# RTC.net
KiCad netlist of a schematic drawn in Altium Designer
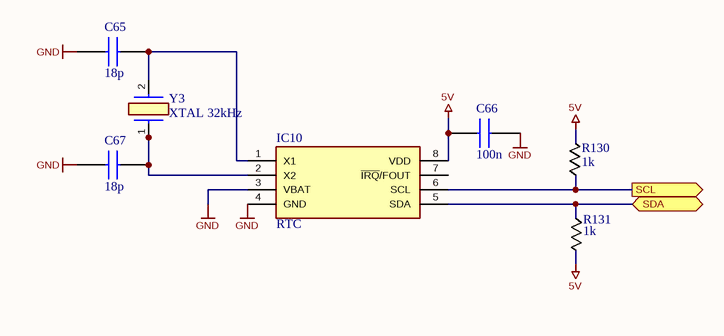
[diagram p0: RTC.SchDoc]

(export (version "E")
  (design (tool "Eeschema 10.0.6"))
  (components
    (comp (ref "C65")
      (value "18p")
      (footprint "0603 CAP")
      (description "CC0603JRNPO9BN180")
      (fields
        (field (name "MANUFACTURER_PART_NUMBER") "GRM188R72A103KA01D")
        (field (name "MOUSER PART NUMBER") "81-GRM188R72A103KA1D")
      )
      (libsource (lib "IGAS Elements") (part "0603 CAP"))
    )
    (comp (ref "C66")
      (value "100n")
      (footprint "0603 CAP")
      (description "CC0603KRX7R9BB104")
      (fields
        (field (name "MANUFACTURER_PART_NUMBER") "GRM188R72A103KA01D")
        (field (name "MOUSER PART NUMBER") "81-GRM188R72A103KA1D")
      )
      (libsource (lib "IGAS Elements") (part "0603 CAP"))
    )
    (comp (ref "C67")
      (value "18p")
      (footprint "0603 CAP")
      (description "CC0603JRNPO9BN180")
      (fields
        (field (name "MANUFACTURER_PART_NUMBER") "GRM188R72A103KA01D")
        (field (name "MOUSER PART NUMBER") "81-GRM188R72A103KA1D")
      )
      (libsource (lib "IGAS Elements") (part "0603 CAP"))
    )
    (comp (ref "IC10")
      (value "RTC")
      (footprint "IGAS Elements:SOIC-8")
      (description "ISL1208IB8Z-TK")
      (fields
        (field (name "MANUFACTURER_PART_NUMBER") "ISL1208IB8Z")
        (field (name "MOUSER PART NUMBER") "968-ISL1208IB8Z")
      )
      (libsource (lib "IGAS Elements") (part "ISL1208IB8Z"))
    )
    (comp (ref "R130")
      (value "1k")
      (footprint "0603 CAP")
      (libsource (lib "IGAS Elements") (part "0603 RES"))
    )
    (comp (ref "R131")
      (value "1k")
      (footprint "0603 CAP")
      (libsource (lib "IGAS Elements") (part "0603 RES"))
    )
    (comp (ref "Y3")
      (value "XTAL 32kHz")
      (footprint "IGAS Elements:NX32 kHz")
      (description "Crystal or Oscillator")
      (fields
        (field (name "MANUFACTURER_PART_NUMBER") "NX3215SA-32.768K-STD-MUA-14")
        (field (name "MOUSER PART NUMBER") "344-NX3215SA32768K14")
      )
      (libsource (lib "IGAS Elements") (part "XTAL 32kHz"))
    )
  )
  (nets
    (net (code "1") (name "/SCL") (class "Default")
      (node (ref "IC10") (pin "6") (pinfunction "SCL_6") (pintype "passive"))
      (node (ref "R130") (pin "1") (pintype "passive"))
    )
    (net (code "2") (name "/SDA") (class "Default")
      (node (ref "IC10") (pin "5") (pinfunction "SDA_5") (pintype "passive"))
      (node (ref "R131") (pin "1") (pintype "passive"))
    )
    (net (code "3") (name "5V") (class "Default")
      (node (ref "C66") (pin "2") (pinfunction "2_2") (pintype "passive"))
      (node (ref "IC10") (pin "8") (pinfunction "VDD_8") (pintype "passive"))
      (node (ref "R130") (pin "2") (pintype "passive"))
      (node (ref "R131") (pin "2") (pintype "passive"))
    )
    (net (code "4") (name "GND") (class "Default")
      (node (ref "C65") (pin "1") (pinfunction "1_1") (pintype "passive"))
      (node (ref "C66") (pin "1") (pinfunction "1_1") (pintype "passive"))
      (node (ref "C67") (pin "1") (pinfunction "1_1") (pintype "passive"))
      (node (ref "IC10") (pin "3") (pinfunction "VBAT_3") (pintype "passive"))
      (node (ref "IC10") (pin "4") (pinfunction "GND_4") (pintype "passive"))
    )
    (net (code "5") (name "Net-(IC10-X1)") (class "Default")
      (node (ref "C65") (pin "2") (pinfunction "2_2") (pintype "passive"))
      (node (ref "IC10") (pin "1") (pinfunction "X1_1") (pintype "passive"))
      (node (ref "Y3") (pin "2") (pinfunction "2_2") (pintype "passive"))
    )
    (net (code "6") (name "Net-(IC10-X2)") (class "Default")
      (node (ref "C67") (pin "2") (pinfunction "2_2") (pintype "passive"))
      (node (ref "IC10") (pin "2") (pinfunction "X2_2") (pintype "passive"))
      (node (ref "Y3") (pin "1") (pinfunction "1_1") (pintype "passive"))
    )
    (net (code "7") (name "unconnected-(IC10-~{IRQ}{slash}FOUT-Pad7)") (class "Default")
      (node (ref "IC10") (pin "7") (pinfunction "~{IRQ}/FOUT_7") (pintype "passive"))
    )
  )
)
